# Arduino_Schematic.net
KiCad netlist of a schematic drawn in Altium Designer
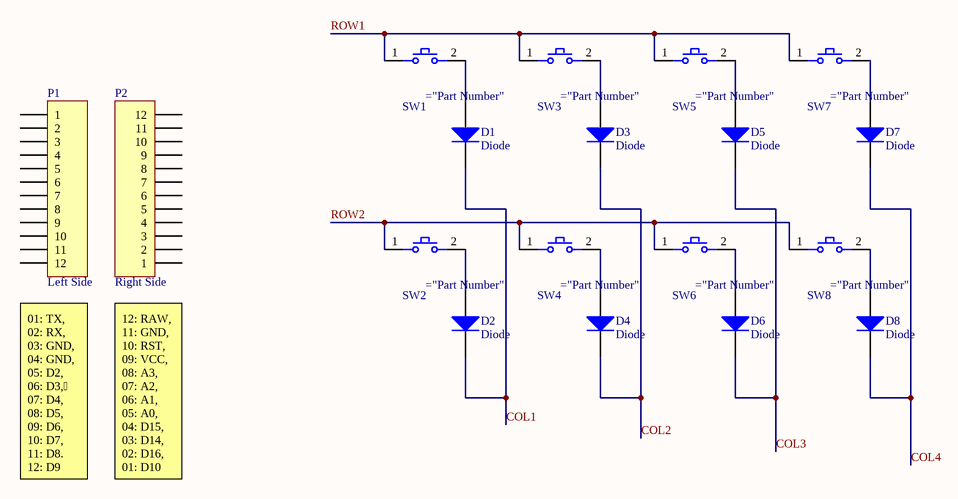
[diagram p0: Arduino_Schematic.SchDoc]

(export (version "E")
  (design (tool "Eeschema 10.0.6"))
  (components
    (comp (ref "D1")
      (value "Diode")
      (footprint "SMC")
      (description "Default Diode")
      (fields (field (name "PUBLISHER") "Altium Limited"))
      (libsource (lib "Miscellaneous Devices") (part "Diode"))
    )
    (comp (ref "D2")
      (value "Diode")
      (footprint "SMC")
      (description "Default Diode")
      (fields (field (name "PUBLISHER") "Altium Limited"))
      (libsource (lib "Miscellaneous Devices") (part "Diode"))
    )
    (comp (ref "D3")
      (value "Diode")
      (footprint "SMC")
      (description "Default Diode")
      (fields (field (name "PUBLISHER") "Altium Limited"))
      (libsource (lib "Miscellaneous Devices") (part "Diode"))
    )
    (comp (ref "D4")
      (value "Diode")
      (footprint "SMC")
      (description "Default Diode")
      (fields (field (name "PUBLISHER") "Altium Limited"))
      (libsource (lib "Miscellaneous Devices") (part "Diode"))
    )
    (comp (ref "D5")
      (value "Diode")
      (footprint "SMC")
      (description "Default Diode")
      (fields (field (name "PUBLISHER") "Altium Limited"))
      (libsource (lib "Miscellaneous Devices") (part "Diode"))
    )
    (comp (ref "D6")
      (value "Diode")
      (footprint "SMC")
      (description "Default Diode")
      (fields (field (name "PUBLISHER") "Altium Limited"))
      (libsource (lib "Miscellaneous Devices") (part "Diode"))
    )
    (comp (ref "D7")
      (value "Diode")
      (footprint "SMC")
      (description "Default Diode")
      (fields (field (name "PUBLISHER") "Altium Limited"))
      (libsource (lib "Miscellaneous Devices") (part "Diode"))
    )
    (comp (ref "D8")
      (value "Diode")
      (footprint "SMC")
      (description "Default Diode")
      (fields (field (name "PUBLISHER") "Altium Limited"))
      (libsource (lib "Miscellaneous Devices") (part "Diode"))
    )
    (comp (ref "P1")
      (value "Left Side")
      (footprint "HDR1X12")
      (description "Header, 12-Pin")
      (fields (field (name "PUBLISHER") "Altium Limited"))
      (libsource (lib "Miscellaneous Connectors") (part "Header 12"))
    )
    (comp (ref "P2")
      (value "Right Side")
      (footprint "HDR1X12")
      (description "Header, 12-Pin")
      (fields (field (name "PUBLISHER") "Altium Limited"))
      (libsource (lib "") (part "Header 12_1"))
    )
    (comp (ref "SW1") (value "MX1A-C1NW") (libsource (lib "Switch_Cherry_MX1A-C1NW_eec") (part "MX1A-C1NW")))
    (comp (ref "SW2") (value "MX1A-C1NW") (libsource (lib "Switch_Cherry_MX1A-C1NW_eec") (part "MX1A-C1NW")))
    (comp (ref "SW3") (value "MX1A-C1NW") (libsource (lib "Switch_Cherry_MX1A-C1NW_eec") (part "MX1A-C1NW")))
    (comp (ref "SW4") (value "MX1A-C1NW") (libsource (lib "Switch_Cherry_MX1A-C1NW_eec") (part "MX1A-C1NW")))
    (comp (ref "SW5") (value "MX1A-C1NW") (libsource (lib "Switch_Cherry_MX1A-C1NW_eec") (part "MX1A-C1NW")))
    (comp (ref "SW6") (value "MX1A-C1NW") (libsource (lib "Switch_Cherry_MX1A-C1NW_eec") (part "MX1A-C1NW")))
    (comp (ref "SW7") (value "MX1A-C1NW") (libsource (lib "Switch_Cherry_MX1A-C1NW_eec") (part "MX1A-C1NW")))
    (comp (ref "SW8") (value "MX1A-C1NW") (libsource (lib "Switch_Cherry_MX1A-C1NW_eec") (part "MX1A-C1NW")))
  )
  (nets
    (net (code "1") (name "/COL1") (class "Default")
      (node (ref "D1") (pin "2") (pinfunction "K_2") (pintype "passive"))
      (node (ref "D2") (pin "2") (pinfunction "K_2") (pintype "passive"))
    )
    (net (code "2") (name "/COL2") (class "Default")
      (node (ref "D3") (pin "2") (pinfunction "K_2") (pintype "passive"))
      (node (ref "D4") (pin "2") (pinfunction "K_2") (pintype "passive"))
    )
    (net (code "3") (name "/COL3") (class "Default")
      (node (ref "D5") (pin "2") (pinfunction "K_2") (pintype "passive"))
      (node (ref "D6") (pin "2") (pinfunction "K_2") (pintype "passive"))
    )
    (net (code "4") (name "/COL4") (class "Default")
      (node (ref "D7") (pin "2") (pinfunction "K_2") (pintype "passive"))
      (node (ref "D8") (pin "2") (pinfunction "K_2") (pintype "passive"))
    )
    (net (code "5") (name "/ROW1") (class "Default")
      (node (ref "SW1") (pin "1") (pinfunction "1_1") (pintype "passive"))
      (node (ref "SW3") (pin "1") (pinfunction "1_1") (pintype "passive"))
      (node (ref "SW5") (pin "1") (pinfunction "1_1") (pintype "passive"))
      (node (ref "SW7") (pin "1") (pinfunction "1_1") (pintype "passive"))
    )
    (net (code "6") (name "/ROW2") (class "Default")
      (node (ref "SW2") (pin "1") (pinfunction "1_1") (pintype "passive"))
      (node (ref "SW4") (pin "1") (pinfunction "1_1") (pintype "passive"))
      (node (ref "SW6") (pin "1") (pinfunction "1_1") (pintype "passive"))
      (node (ref "SW8") (pin "1") (pinfunction "1_1") (pintype "passive"))
    )
    (net (code "7") (name "Net-(D1-A)") (class "Default")
      (node (ref "D1") (pin "1") (pinfunction "A_1") (pintype "passive"))
      (node (ref "SW1") (pin "2") (pinfunction "2_2") (pintype "passive"))
    )
    (net (code "8") (name "Net-(D2-A)") (class "Default")
      (node (ref "D2") (pin "1") (pinfunction "A_1") (pintype "passive"))
      (node (ref "SW2") (pin "2") (pinfunction "2_2") (pintype "passive"))
    )
    (net (code "9") (name "Net-(D3-A)") (class "Default")
      (node (ref "D3") (pin "1") (pinfunction "A_1") (pintype "passive"))
      (node (ref "SW3") (pin "2") (pinfunction "2_2") (pintype "passive"))
    )
    (net (code "10") (name "Net-(D4-A)") (class "Default")
      (node (ref "D4") (pin "1") (pinfunction "A_1") (pintype "passive"))
      (node (ref "SW4") (pin "2") (pinfunction "2_2") (pintype "passive"))
    )
    (net (code "11") (name "Net-(D5-A)") (class "Default")
      (node (ref "D5") (pin "1") (pinfunction "A_1") (pintype "passive"))
      (node (ref "SW5") (pin "2") (pinfunction "2_2") (pintype "passive"))
    )
    (net (code "12") (name "Net-(D6-A)") (class "Default")
      (node (ref "D6") (pin "1") (pinfunction "A_1") (pintype "passive"))
      (node (ref "SW6") (pin "2") (pinfunction "2_2") (pintype "passive"))
    )
    (net (code "13") (name "Net-(D7-A)") (class "Default")
      (node (ref "D7") (pin "1") (pinfunction "A_1") (pintype "passive"))
      (node (ref "SW7") (pin "2") (pinfunction "2_2") (pintype "passive"))
    )
    (net (code "14") (name "Net-(D8-A)") (class "Default")
      (node (ref "D8") (pin "1") (pinfunction "A_1") (pintype "passive"))
      (node (ref "SW8") (pin "2") (pinfunction "2_2") (pintype "passive"))
    )
    (net (code "15") (name "unconnected-(P1-Pad1)") (class "Default")
      (node (ref "P1") (pin "1") (pinfunction "1_1") (pintype "passive"))
    )
    (net (code "16") (name "unconnected-(P1-Pad2)") (class "Default")
      (node (ref "P1") (pin "2") (pinfunction "2_2") (pintype "passive"))
    )
    (net (code "17") (name "unconnected-(P1-Pad3)") (class "Default")
      (node (ref "P1") (pin "3") (pinfunction "3_3") (pintype "passive"))
    )
    (net (code "18") (name "unconnected-(P1-Pad4)") (class "Default")
      (node (ref "P1") (pin "4") (pinfunction "4_4") (pintype "passive"))
    )
    (net (code "19") (name "unconnected-(P1-Pad5)") (class "Default")
      (node (ref "P1") (pin "5") (pinfunction "5_5") (pintype "passive"))
    )
    (net (code "20") (name "unconnected-(P1-Pad6)") (class "Default")
      (node (ref "P1") (pin "6") (pinfunction "6_6") (pintype "passive"))
    )
    (net (code "21") (name "unconnected-(P1-Pad7)") (class "Default")
      (node (ref "P1") (pin "7") (pinfunction "7_7") (pintype "passive"))
    )
    (net (code "22") (name "unconnected-(P1-Pad8)") (class "Default")
      (node (ref "P1") (pin "8") (pinfunction "8_8") (pintype "passive"))
    )
    (net (code "23") (name "unconnected-(P1-Pad9)") (class "Default")
      (node (ref "P1") (pin "9") (pinfunction "9_9") (pintype "passive"))
    )
    (net (code "24") (name "unconnected-(P1-Pad10)") (class "Default")
      (node (ref "P1") (pin "10") (pinfunction "10_10") (pintype "passive"))
    )
    (net (code "25") (name "unconnected-(P1-Pad11)") (class "Default")
      (node (ref "P1") (pin "11") (pinfunction "11_11") (pintype "passive"))
    )
    (net (code "26") (name "unconnected-(P1-Pad12)") (class "Default")
      (node (ref "P1") (pin "12") (pinfunction "12_12") (pintype "passive"))
    )
    (net (code "27") (name "unconnected-(P2-Pad1)") (class "Default")
      (node (ref "P2") (pin "1") (pinfunction "1_1") (pintype "passive"))
    )
    (net (code "28") (name "unconnected-(P2-Pad2)") (class "Default")
      (node (ref "P2") (pin "2") (pinfunction "2_2") (pintype "passive"))
    )
    (net (code "29") (name "unconnected-(P2-Pad3)") (class "Default")
      (node (ref "P2") (pin "3") (pinfunction "3_3") (pintype "passive"))
    )
    (net (code "30") (name "unconnected-(P2-Pad4)") (class "Default")
      (node (ref "P2") (pin "4") (pinfunction "4_4") (pintype "passive"))
    )
    (net (code "31") (name "unconnected-(P2-Pad5)") (class "Default")
      (node (ref "P2") (pin "5") (pinfunction "5_5") (pintype "passive"))
    )
    (net (code "32") (name "unconnected-(P2-Pad6)") (class "Default")
      (node (ref "P2") (pin "6") (pinfunction "6_6") (pintype "passive"))
    )
    (net (code "33") (name "unconnected-(P2-Pad7)") (class "Default")
      (node (ref "P2") (pin "7") (pinfunction "7_7") (pintype "passive"))
    )
    (net (code "34") (name "unconnected-(P2-Pad8)") (class "Default")
      (node (ref "P2") (pin "8") (pinfunction "8_8") (pintype "passive"))
    )
    (net (code "35") (name "unconnected-(P2-Pad9)") (class "Default")
      (node (ref "P2") (pin "9") (pinfunction "9_9") (pintype "passive"))
    )
    (net (code "36") (name "unconnected-(P2-Pad10)") (class "Default")
      (node (ref "P2") (pin "10") (pinfunction "10_10") (pintype "passive"))
    )
    (net (code "37") (name "unconnected-(P2-Pad11)") (class "Default")
      (node (ref "P2") (pin "11") (pinfunction "11_11") (pintype "passive"))
    )
    (net (code "38") (name "unconnected-(P2-Pad12)") (class "Default")
      (node (ref "P2") (pin "12") (pinfunction "12_12") (pintype "passive"))
    )
  )
)
